# MAX3232.net
KiCad netlist of a schematic drawn in EAGLE
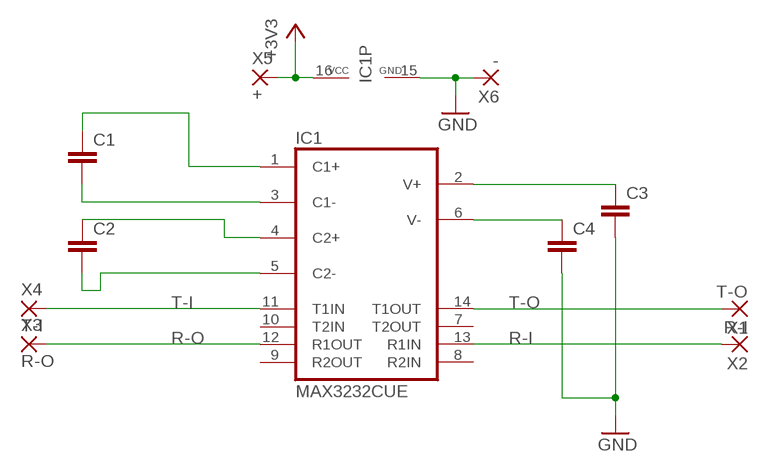
[diagram p0: schematic, sheet 1]

(export (version "E")
  (design (tool "Eeschema 10.0.6"))
  (components
    (comp (ref "C1")
      (value "CAP_0805")
      (footprint "eagle-import:CAP0805")
      (libsource (lib "eagle-import") (part "CAP_0805"))
    )
    (comp (ref "C2")
      (value "CAP_0805")
      (footprint "eagle-import:CAP0805")
      (libsource (lib "eagle-import") (part "CAP_0805"))
    )
    (comp (ref "C3")
      (value "CAP_0805")
      (footprint "eagle-import:CAP0805")
      (libsource (lib "eagle-import") (part "CAP_0805"))
    )
    (comp (ref "C4")
      (value "CAP_0805")
      (footprint "eagle-import:CAP0805")
      (libsource (lib "eagle-import") (part "CAP_0805"))
    )
    (comp (ref "IC1")
      (value "MAX3232CUE")
      (footprint "eagle-import:TSSOP16")
      (fields (field (name "MF") "MAXIM") (field (name "MPN") "MAX3232CUE+"))
      (libsource (lib "eagle-import") (part "MAX3232UEC"))
    )
    (comp (ref "X1")
      (value "T-O")
      (footprint "eagle-import:PAD-1.27X2.54")
      (libsource (lib "eagle-import") (part "WIREPAD-SMD2"))
    )
    (comp (ref "X2")
      (value "R-I")
      (footprint "eagle-import:PAD-1.27X2.54")
      (libsource (lib "eagle-import") (part "WIREPAD-SMD2"))
    )
    (comp (ref "X3")
      (value "R-O")
      (footprint "eagle-import:PAD-1.27X2.54")
      (libsource (lib "eagle-import") (part "WIREPAD-SMD2"))
    )
    (comp (ref "X4")
      (value "T-I")
      (footprint "eagle-import:PAD-1.27X2.54")
      (libsource (lib "eagle-import") (part "WIREPAD-SMD2"))
    )
    (comp (ref "X5")
      (value "+")
      (footprint "eagle-import:PAD-1.27X2.54")
      (libsource (lib "eagle-import") (part "WIREPAD-SMD2"))
    )
    (comp (ref "X6")
      (value "-")
      (footprint "eagle-import:PAD-1.27X2.54")
      (libsource (lib "eagle-import") (part "WIREPAD-SMD2"))
    )
  )
  (nets
    (net (code "1") (name "+3V3") (class "Default")
      (node (ref "IC1") (pin "16") (pinfunction "VCC_16") (pintype "power_in"))
      (node (ref "X5") (pin "P$1") (pinfunction "P_P$1") (pintype "passive"))
    )
    (net (code "2") (name "/R-I") (class "Default")
      (node (ref "IC1") (pin "13") (pinfunction "R1IN_13") (pintype "input"))
      (node (ref "X2") (pin "P$1") (pinfunction "P_P$1") (pintype "passive"))
    )
    (net (code "3") (name "/R-O") (class "Default")
      (node (ref "IC1") (pin "12") (pinfunction "R1OUT_12") (pintype "output"))
      (node (ref "X3") (pin "P$1") (pinfunction "P_P$1") (pintype "passive"))
    )
    (net (code "4") (name "/T-I") (class "Default")
      (node (ref "IC1") (pin "11") (pinfunction "T1IN_11") (pintype "input"))
      (node (ref "X4") (pin "P$1") (pinfunction "P_P$1") (pintype "passive"))
    )
    (net (code "5") (name "/T-O") (class "Default")
      (node (ref "IC1") (pin "14") (pinfunction "T1OUT_14") (pintype "output"))
      (node (ref "X1") (pin "P$1") (pinfunction "P_P$1") (pintype "passive"))
    )
    (net (code "6") (name "GND") (class "Default")
      (node (ref "C3") (pin "2") (pinfunction "2_2") (pintype "passive"))
      (node (ref "C4") (pin "2") (pinfunction "2_2") (pintype "passive"))
      (node (ref "IC1") (pin "15") (pinfunction "GND_15") (pintype "power_in"))
      (node (ref "X6") (pin "P$1") (pinfunction "P_P$1") (pintype "passive"))
    )
    (net (code "7") (name "Net-(IC1A-C1+)") (class "Default")
      (node (ref "C1") (pin "1") (pinfunction "1_1") (pintype "passive"))
      (node (ref "IC1") (pin "1") (pinfunction "C1+_1") (pintype "bidirectional"))
    )
    (net (code "8") (name "Net-(IC1A-C1-)") (class "Default")
      (node (ref "C1") (pin "2") (pinfunction "2_2") (pintype "passive"))
      (node (ref "IC1") (pin "3") (pinfunction "C1-_3") (pintype "bidirectional"))
    )
    (net (code "9") (name "Net-(IC1A-C2+)") (class "Default")
      (node (ref "C2") (pin "1") (pinfunction "1_1") (pintype "passive"))
      (node (ref "IC1") (pin "4") (pinfunction "C2+_4") (pintype "bidirectional"))
    )
    (net (code "10") (name "Net-(IC1A-C2-)") (class "Default")
      (node (ref "C2") (pin "2") (pinfunction "2_2") (pintype "passive"))
      (node (ref "IC1") (pin "5") (pinfunction "C2-_5") (pintype "bidirectional"))
    )
    (net (code "11") (name "Net-(IC1A-V+)") (class "Default")
      (node (ref "C3") (pin "1") (pinfunction "1_1") (pintype "passive"))
      (node (ref "IC1") (pin "2") (pinfunction "V+_2") (pintype "bidirectional"))
    )
    (net (code "12") (name "Net-(IC1A-V-)") (class "Default")
      (node (ref "C4") (pin "1") (pinfunction "1_1") (pintype "passive"))
      (node (ref "IC1") (pin "6") (pinfunction "V-_6") (pintype "bidirectional"))
    )
    (net (code "13") (name "unconnected-(IC1A-R2IN-Pad8)") (class "Default")
      (node (ref "IC1") (pin "8") (pinfunction "R2IN_8") (pintype "input"))
    )
    (net (code "14") (name "unconnected-(IC1A-R2OUT-Pad9)") (class "Default")
      (node (ref "IC1") (pin "9") (pinfunction "R2OUT_9") (pintype "output"))
    )
    (net (code "15") (name "unconnected-(IC1A-T2IN-Pad10)") (class "Default")
      (node (ref "IC1") (pin "10") (pinfunction "T2IN_10") (pintype "input"))
    )
    (net (code "16") (name "unconnected-(IC1A-T2OUT-Pad7)") (class "Default")
      (node (ref "IC1") (pin "7") (pinfunction "T2OUT_7") (pintype "output"))
    )
  )
)
